# Version_1.net
KiCad netlist of a schematic drawn in EAGLE
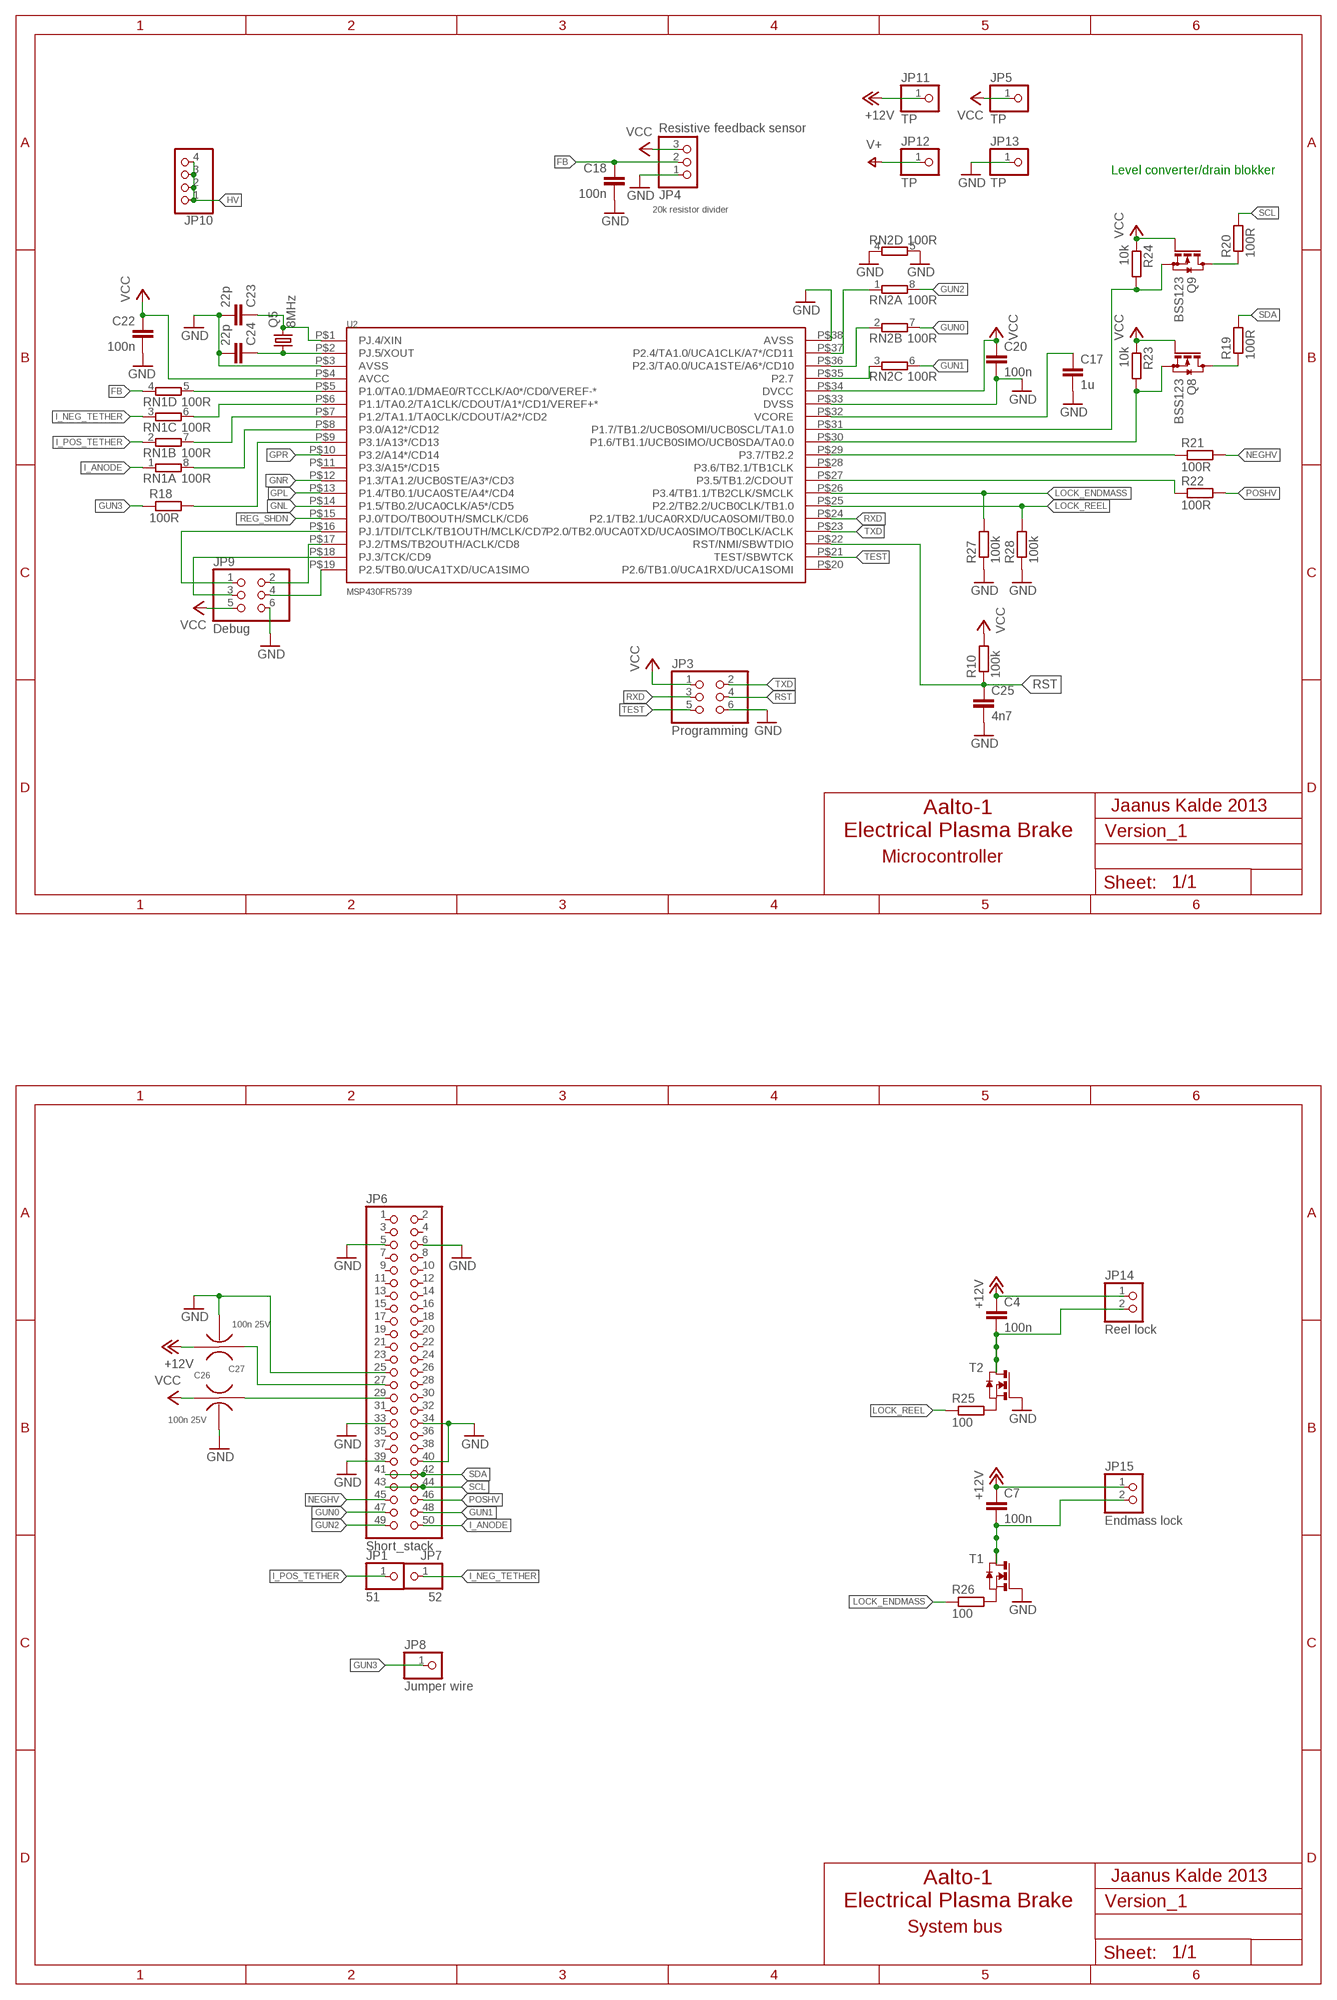
[diagram p0: schematic, sheet 1, part 1 of 2]
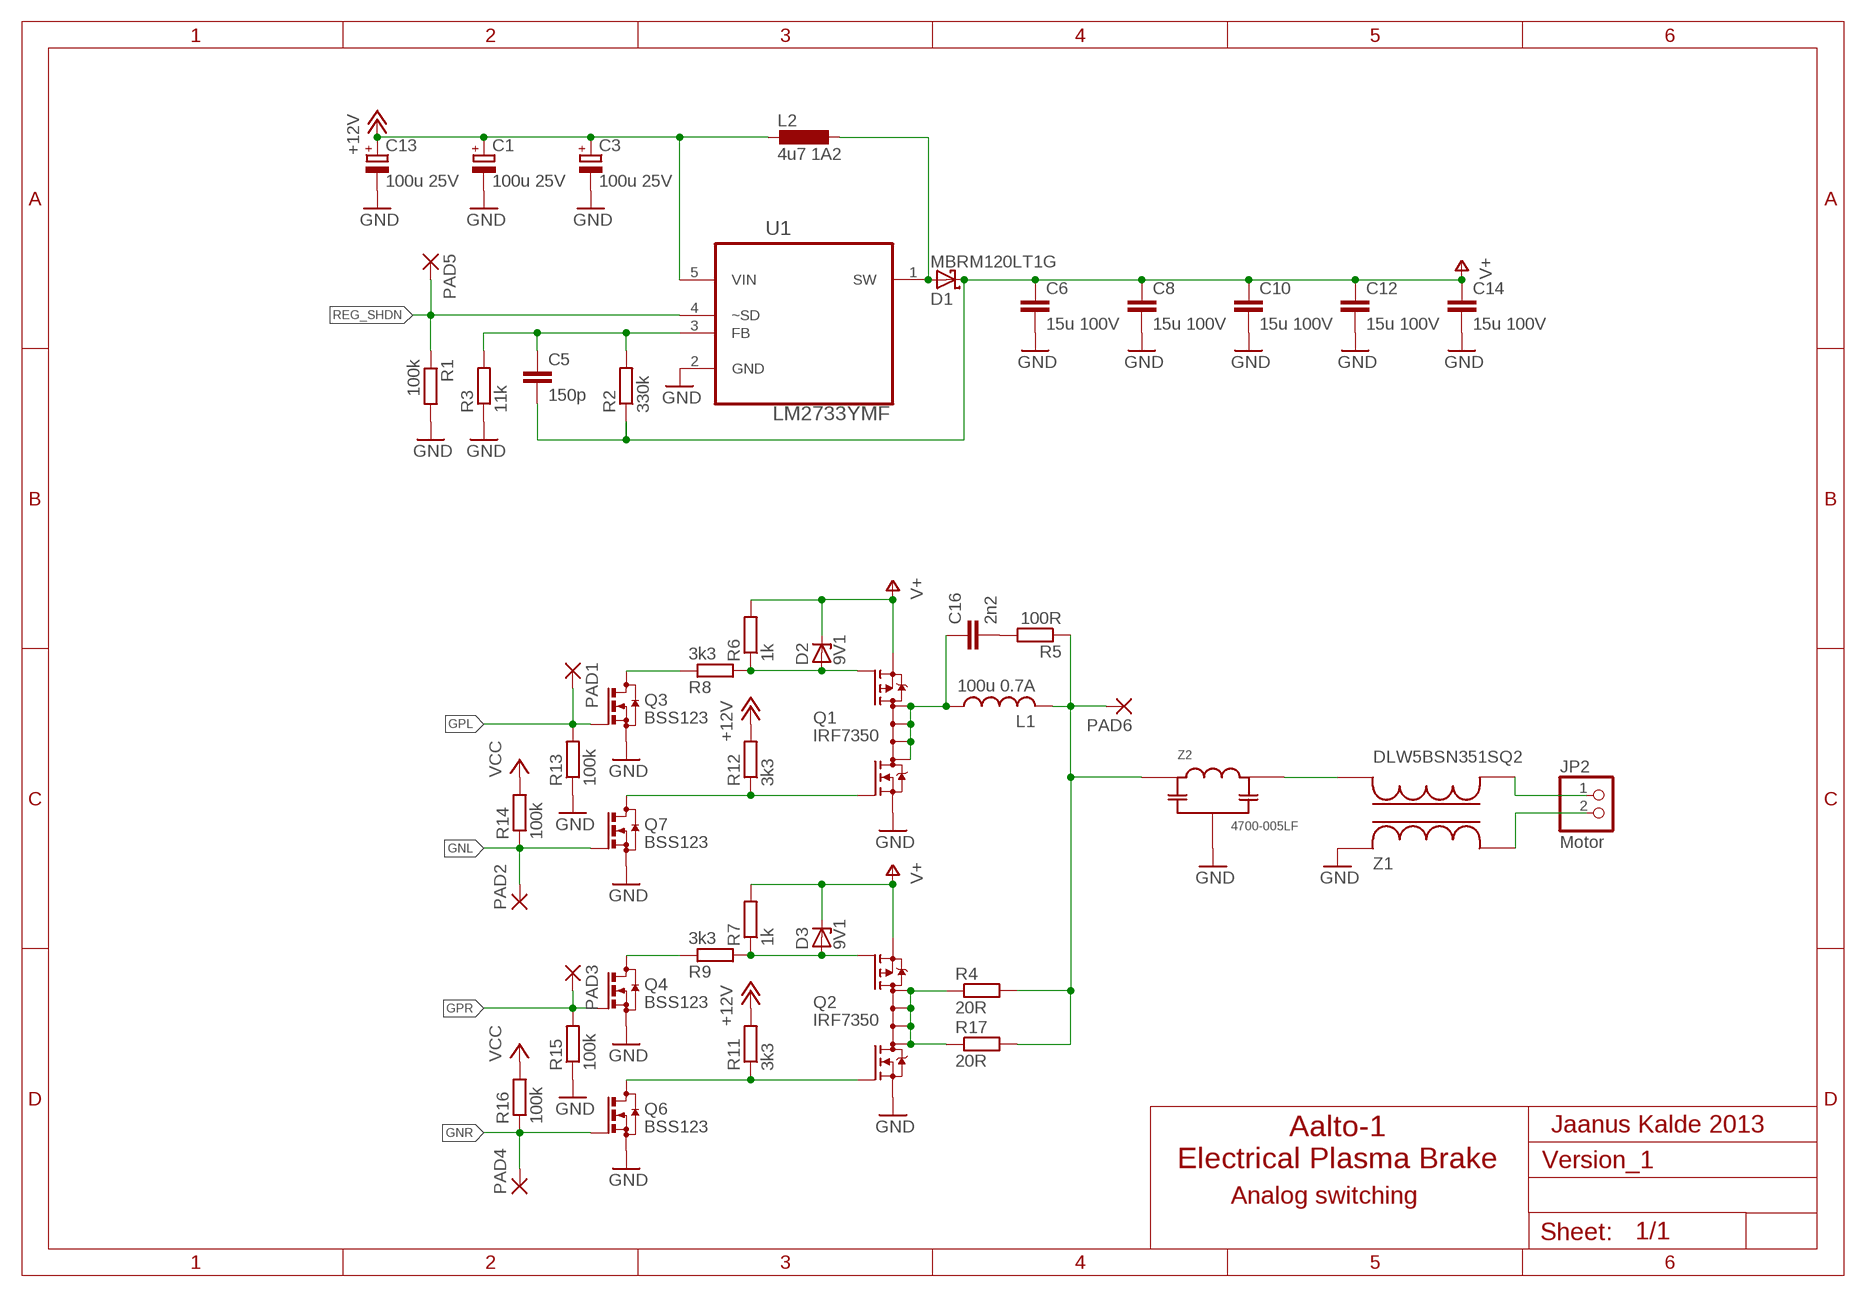
[diagram p1: schematic, sheet 1, part 2 of 2]

(export (version "E")
  (design (tool "Eeschema 10.0.6"))
  (components
    (comp (ref "C1")
      (value "100u 25V")
      (footprint "eagle-import:SMC_E")
      (libsource (lib "eagle-import") (part "CPOL-EUSMCE"))
    )
    (comp (ref "C3")
      (value "100u 25V")
      (footprint "eagle-import:SMC_E")
      (libsource (lib "eagle-import") (part "CPOL-EUSMCE"))
    )
    (comp (ref "C4")
      (value "100n")
      (footprint "eagle-import:C0603")
      (libsource (lib "eagle-import") (part "C-EUC0603"))
    )
    (comp (ref "C5")
      (value "150p")
      (footprint "eagle-import:C0603K")
      (libsource (lib "eagle-import") (part "C-EUC0603K"))
    )
    (comp (ref "C6")
      (value "15u 100V")
      (footprint "eagle-import:C2220K")
      (libsource (lib "eagle-import") (part "C-EUC2220K"))
    )
    (comp (ref "C7")
      (value "100n")
      (footprint "eagle-import:C0603")
      (libsource (lib "eagle-import") (part "C-EUC0603"))
    )
    (comp (ref "C8")
      (value "15u 100V")
      (footprint "eagle-import:C2220K")
      (libsource (lib "eagle-import") (part "C-EUC2220K"))
    )
    (comp (ref "C10")
      (value "15u 100V")
      (footprint "eagle-import:C2220K")
      (libsource (lib "eagle-import") (part "C-EUC2220K"))
    )
    (comp (ref "C12")
      (value "15u 100V")
      (footprint "eagle-import:C2220K")
      (libsource (lib "eagle-import") (part "C-EUC2220K"))
    )
    (comp (ref "C13")
      (value "100u 25V")
      (footprint "eagle-import:SMC_E")
      (libsource (lib "eagle-import") (part "CPOL-EUSMCE"))
    )
    (comp (ref "C14")
      (value "15u 100V")
      (footprint "eagle-import:C2220K")
      (libsource (lib "eagle-import") (part "C-EUC2220K"))
    )
    (comp (ref "C16")
      (value "2n2")
      (footprint "eagle-import:C0805")
      (libsource (lib "eagle-import") (part "C-EUC0805"))
    )
    (comp (ref "C17")
      (value "1u")
      (footprint "eagle-import:C0603K")
      (libsource (lib "eagle-import") (part "C-EUC0603K"))
    )
    (comp (ref "C18")
      (value "100n")
      (footprint "eagle-import:C0603K")
      (libsource (lib "eagle-import") (part "C-EUC0603K"))
    )
    (comp (ref "C20")
      (value "100n")
      (footprint "eagle-import:C0603K")
      (libsource (lib "eagle-import") (part "C-EUC0603K"))
    )
    (comp (ref "C22")
      (value "100n")
      (footprint "eagle-import:C0603")
      (libsource (lib "eagle-import") (part "C-EUC0603"))
    )
    (comp (ref "C23")
      (value "22p")
      (footprint "eagle-import:C0603")
      (libsource (lib "eagle-import") (part "C-EUC0603"))
    )
    (comp (ref "C24")
      (value "22p")
      (footprint "eagle-import:C0603")
      (libsource (lib "eagle-import") (part "C-EUC0603"))
    )
    (comp (ref "C25")
      (value "4n7")
      (footprint "eagle-import:C0603")
      (libsource (lib "eagle-import") (part "C-EUC0603"))
    )
    (comp (ref "C26")
      (value "100n 25V")
      (footprint "eagle-import:0805-3TERM")
      (libsource (lib "eagle-import") (part "CAP-3TERM"))
    )
    (comp (ref "C27")
      (value "100n 25V")
      (footprint "eagle-import:0805-3TERM")
      (libsource (lib "eagle-import") (part "CAP-3TERM"))
    )
    (comp (ref "D1")
      (value "MBRM120LT1G")
      (footprint "eagle-import:POWERMITE")
      (libsource (lib "eagle-import") (part "MBRM120LT1G"))
    )
    (comp (ref "D2")
      (value "9V1")
      (footprint "eagle-import:SOD80C")
      (libsource (lib "eagle-import") (part "ZENER-DIODESOD80C"))
    )
    (comp (ref "D3")
      (value "9V1")
      (footprint "eagle-import:SOD80C")
      (libsource (lib "eagle-import") (part "ZENER-DIODESOD80C"))
    )
    (comp (ref "JP1")
      (value "51")
      (footprint "eagle-import:1X01")
      (libsource (lib "eagle-import") (part "PINHD-1X1"))
    )
    (comp (ref "JP2")
      (value "Motor")
      (footprint "eagle-import:1X02M")
      (libsource (lib "eagle-import") (part "PINHD-1X02_2.00"))
    )
    (comp (ref "JP3")
      (value "Programming")
      (footprint "eagle-import:MICROMATCH-6")
      (libsource (lib "eagle-import") (part "PINHD-2X03_MICROMATCH"))
    )
    (comp (ref "JP4")
      (value "Resistive feedback sensor")
      (footprint "eagle-import:1X03M")
      (libsource (lib "eagle-import") (part "PINHD-1X03_2.00"))
    )
    (comp (ref "JP5")
      (value "TP")
      (footprint "eagle-import:1X01")
      (libsource (lib "eagle-import") (part "PINHD-1X1"))
    )
    (comp (ref "JP6")
      (value "Short_stack")
      (footprint "eagle-import:2X25")
      (libsource (lib "eagle-import") (part "PINHD-2X25"))
    )
    (comp (ref "JP7")
      (value "52")
      (footprint "eagle-import:1X01")
      (libsource (lib "eagle-import") (part "PINHD-1X1"))
    )
    (comp (ref "JP8")
      (value "Jumper wire")
      (footprint "eagle-import:1X01")
      (libsource (lib "eagle-import") (part "PINHD-1X1"))
    )
    (comp (ref "JP9")
      (value "Debug")
      (footprint "eagle-import:MICROMATCH-6")
      (libsource (lib "eagle-import") (part "PINHD-2X03_MICROMATCH"))
    )
    (comp (ref "JP10")
      (value "PINHD-1X4")
      (footprint "eagle-import:1X04")
      (libsource (lib "eagle-import") (part "PINHD-1X4"))
    )
    (comp (ref "JP11")
      (value "TP")
      (footprint "eagle-import:1X01")
      (libsource (lib "eagle-import") (part "PINHD-1X1"))
    )
    (comp (ref "JP12")
      (value "TP")
      (footprint "eagle-import:1X01")
      (libsource (lib "eagle-import") (part "PINHD-1X1"))
    )
    (comp (ref "JP13")
      (value "TP")
      (footprint "eagle-import:1X01")
      (libsource (lib "eagle-import") (part "PINHD-1X1"))
    )
    (comp (ref "JP14")
      (value "Reel lock")
      (footprint "eagle-import:1X02M")
      (libsource (lib "eagle-import") (part "PINHD-1X02_2.00"))
    )
    (comp (ref "JP15")
      (value "Endmass lock")
      (footprint "eagle-import:1X02M")
      (libsource (lib "eagle-import") (part "PINHD-1X02_2.00"))
    )
    (comp (ref "L1")
      (value "100u 0.7A")
      (footprint "eagle-import:L-SMD-7.3")
      (libsource (lib "eagle-import") (part "L-SMD-7.3"))
    )
    (comp (ref "L2")
      (value "4u7 1A2")
      (footprint "eagle-import:SRR4011")
      (libsource (lib "eagle-import") (part "SRR4011"))
    )
    (comp (ref "PAD1")
      (value "WIREPAD1,6/0,8")
      (footprint "eagle-import:1,6_0,8")
      (libsource (lib "eagle-import") (part "WIREPAD1,6/0,8"))
    )
    (comp (ref "PAD2")
      (value "WIREPAD1,6/0,8")
      (footprint "eagle-import:1,6_0,8")
      (libsource (lib "eagle-import") (part "WIREPAD1,6/0,8"))
    )
    (comp (ref "PAD3")
      (value "WIREPAD1,6/0,8")
      (footprint "eagle-import:1,6_0,8")
      (libsource (lib "eagle-import") (part "WIREPAD1,6/0,8"))
    )
    (comp (ref "PAD4")
      (value "WIREPAD1,6/0,8")
      (footprint "eagle-import:1,6_0,8")
      (libsource (lib "eagle-import") (part "WIREPAD1,6/0,8"))
    )
    (comp (ref "PAD5")
      (value "WIREPAD1,6/0,8")
      (footprint "eagle-import:1,6_0,8")
      (libsource (lib "eagle-import") (part "WIREPAD1,6/0,8"))
    )
    (comp (ref "PAD6")
      (value "WIREPAD1,6/0,8")
      (footprint "eagle-import:1,6_0,8")
      (libsource (lib "eagle-import") (part "WIREPAD1,6/0,8"))
    )
    (comp (ref "Q1")
      (value "IRF7350")
      (footprint "eagle-import:SO08-IRF")
      (libsource (lib "eagle-import") (part "IRF7389"))
    )
    (comp (ref "Q2")
      (value "IRF7350")
      (footprint "eagle-import:SO08-IRF")
      (libsource (lib "eagle-import") (part "IRF7389"))
    )
    (comp (ref "Q3")
      (value "BSS123")
      (footprint "eagle-import:SOT23")
      (libsource (lib "eagle-import") (part "BSS123"))
    )
    (comp (ref "Q4")
      (value "BSS123")
      (footprint "eagle-import:SOT23")
      (libsource (lib "eagle-import") (part "BSS123"))
    )
    (comp (ref "Q5")
      (value "8MHz")
      (footprint "eagle-import:HC49U-V")
      (libsource (lib "eagle-import") (part "CRYSTALHC49UV"))
    )
    (comp (ref "Q6")
      (value "BSS123")
      (footprint "eagle-import:SOT23")
      (libsource (lib "eagle-import") (part "BSS123"))
    )
    (comp (ref "Q7")
      (value "BSS123")
      (footprint "eagle-import:SOT23")
      (libsource (lib "eagle-import") (part "BSS123"))
    )
    (comp (ref "Q8")
      (value "BSS123")
      (footprint "eagle-import:SOT23")
      (libsource (lib "eagle-import") (part "BSS123"))
    )
    (comp (ref "Q9")
      (value "BSS123")
      (footprint "eagle-import:SOT23")
      (libsource (lib "eagle-import") (part "BSS123"))
    )
    (comp (ref "R1")
      (value "100k")
      (footprint "eagle-import:R0603")
      (libsource (lib "eagle-import") (part "R-EU_R0603"))
    )
    (comp (ref "R2")
      (value "330k")
      (footprint "eagle-import:R0603")
      (libsource (lib "eagle-import") (part "R-EU_R0603"))
    )
    (comp (ref "R3")
      (value "11k")
      (footprint "eagle-import:R0603")
      (libsource (lib "eagle-import") (part "R-EU_R0603"))
    )
    (comp (ref "R4")
      (value "20R")
      (footprint "eagle-import:R2512")
      (libsource (lib "eagle-import") (part "R-EU_R2512"))
    )
    (comp (ref "R5")
      (value "100R")
      (footprint "eagle-import:R0805")
      (libsource (lib "eagle-import") (part "R-EU_R0805"))
    )
    (comp (ref "R6")
      (value "1k")
      (footprint "eagle-import:R0805")
      (libsource (lib "eagle-import") (part "R-EU_R0805"))
    )
    (comp (ref "R7")
      (value "1k")
      (footprint "eagle-import:R0805")
      (libsource (lib "eagle-import") (part "R-EU_R0805"))
    )
    (comp (ref "R8")
      (value "3k3")
      (footprint "eagle-import:R0805")
      (libsource (lib "eagle-import") (part "R-EU_R0805"))
    )
    (comp (ref "R9")
      (value "3k3")
      (footprint "eagle-import:R0805")
      (libsource (lib "eagle-import") (part "R-EU_R0805"))
    )
    (comp (ref "R10")
      (value "100k")
      (footprint "eagle-import:R0603")
      (libsource (lib "eagle-import") (part "R-EU_R0603"))
    )
    (comp (ref "R11")
      (value "3k3")
      (footprint "eagle-import:R0805")
      (libsource (lib "eagle-import") (part "R-EU_R0805"))
    )
    (comp (ref "R12")
      (value "3k3")
      (footprint "eagle-import:R0805")
      (libsource (lib "eagle-import") (part "R-EU_R0805"))
    )
    (comp (ref "R13")
      (value "100k")
      (footprint "eagle-import:R0603")
      (libsource (lib "eagle-import") (part "R-EU_R0603"))
    )
    (comp (ref "R14")
      (value "100k")
      (footprint "eagle-import:R0603")
      (libsource (lib "eagle-import") (part "R-EU_R0603"))
    )
    (comp (ref "R15")
      (value "100k")
      (footprint "eagle-import:R0603")
      (libsource (lib "eagle-import") (part "R-EU_R0603"))
    )
    (comp (ref "R16")
      (value "100k")
      (footprint "eagle-import:R0603")
      (libsource (lib "eagle-import") (part "R-EU_R0603"))
    )
    (comp (ref "R17")
      (value "20R")
      (footprint "eagle-import:R2512")
      (libsource (lib "eagle-import") (part "R-EU_R2512"))
    )
    (comp (ref "R18")
      (value "100R")
      (footprint "eagle-import:R0603")
      (libsource (lib "eagle-import") (part "R-EU_R0603"))
    )
    (comp (ref "R19")
      (value "100R")
      (footprint "eagle-import:R0603")
      (libsource (lib "eagle-import") (part "R-EU_R0603"))
    )
    (comp (ref "R20")
      (value "100R")
      (footprint "eagle-import:R0603")
      (libsource (lib "eagle-import") (part "R-EU_R0603"))
    )
    (comp (ref "R21")
      (value "100R")
      (footprint "eagle-import:R0603")
      (libsource (lib "eagle-import") (part "R-EU_R0603"))
    )
    (comp (ref "R22")
      (value "100R")
      (footprint "eagle-import:R0603")
      (libsource (lib "eagle-import") (part "R-EU_R0603"))
    )
    (comp (ref "R23")
      (value "10k")
      (footprint "eagle-import:R0603")
      (libsource (lib "eagle-import") (part "R-EU_R0603"))
    )
    (comp (ref "R24")
      (value "10k")
      (footprint "eagle-import:R0603")
      (libsource (lib "eagle-import") (part "R-EU_R0603"))
    )
    (comp (ref "R25")
      (value "100")
      (footprint "eagle-import:R0603")
      (libsource (lib "eagle-import") (part "R-EU_R0603"))
    )
    (comp (ref "R26")
      (value "100")
      (footprint "eagle-import:R0603")
      (libsource (lib "eagle-import") (part "R-EU_R0603"))
    )
    (comp (ref "R27")
      (value "100k")
      (footprint "eagle-import:R0603")
      (libsource (lib "eagle-import") (part "R-EU_R0603"))
    )
    (comp (ref "R28")
      (value "100k")
      (footprint "eagle-import:R0603")
      (libsource (lib "eagle-import") (part "R-EU_R0603"))
    )
    (comp (ref "RN1")
      (value "100R")
      (footprint "eagle-import:EXBN8V")
      (fields (field (name "OC_FARNELL") "unknown") (field (name "OC_NEWARK") "unknown"))
      (libsource (lib "eagle-import") (part "4R-NEXBN8V"))
    )
    (comp (ref "RN2")
      (value "100R")
      (footprint "eagle-import:EXBN8V")
      (libsource (lib "eagle-import") (part "4R-NEXBN8V"))
    )
    (comp (ref "T1")
      (value "NMOSSOT23-6")
      (footprint "eagle-import:SOT23-6")
      (libsource (lib "eagle-import") (part "NMOSSOT23-6"))
    )
    (comp (ref "T2")
      (value "NMOSSOT23-6")
      (footprint "eagle-import:SOT23-6")
      (fields (field (name "OC_FARNELL") "unknown") (field (name "OC_NEWARK") "unknown"))
      (libsource (lib "eagle-import") (part "NMOSSOT23-6"))
    )
    (comp (ref "U1")
      (value "LM2733YMF")
      (footprint "eagle-import:SOT95P284X119-5N")
      (libsource (lib "eagle-import") (part "LM2733YMF"))
    )
    (comp (ref "U2")
      (value "MSP430FR5739")
      (footprint "eagle-import:TSSOP38")
      (libsource (lib "eagle-import") (part "MSP430FR5739"))
    )
    (comp (ref "Z1")
      (value "DLW5BSN351SQ2")
      (footprint "eagle-import:DLW5BS")
      (libsource (lib "eagle-import") (part "DLW5BS"))
    )
    (comp (ref "Z2")
      (value "4700-005LF")
      (footprint "eagle-import:FILTER-PI")
      (libsource (lib "eagle-import") (part "FILTER-PI"))
    )
  )
  (nets
    (net (code "1") (name "+12V") (class "Default")
      (node (ref "C1") (pin "+") (pinfunction "+_+") (pintype "passive"))
      (node (ref "C13") (pin "+") (pinfunction "+_+") (pintype "passive"))
      (node (ref "C26") (pin "P$1") (pinfunction "P$1_P$1") (pintype "bidirectional"))
      (node (ref "C3") (pin "+") (pinfunction "+_+") (pintype "passive"))
      (node (ref "C4") (pin "1") (pinfunction "1_1") (pintype "passive"))
      (node (ref "C7") (pin "1") (pinfunction "1_1") (pintype "passive"))
      (node (ref "JP11") (pin "1") (pinfunction "1_1") (pintype "passive"))
      (node (ref "JP14") (pin "1") (pinfunction "1_1") (pintype "passive"))
      (node (ref "JP15") (pin "1") (pinfunction "1_1") (pintype "passive"))
      (node (ref "L2") (pin "P$1") (pinfunction "1_P$1") (pintype "passive"))
      (node (ref "R11") (pin "2") (pinfunction "2_2") (pintype "passive"))
      (node (ref "R12") (pin "2") (pinfunction "2_2") (pintype "passive"))
      (node (ref "U1") (pin "5") (pinfunction "VIN_5") (pintype "power_in"))
    )
    (net (code "2") (name "FB") (class "Default")
      (node (ref "C18") (pin "1") (pinfunction "1_1") (pintype "passive"))
      (node (ref "JP4") (pin "2") (pinfunction "2_2") (pintype "passive"))
      (node (ref "RN1") (pin "4") (pinfunction "1_4") (pintype "passive"))
    )
    (net (code "3") (name "GND") (class "Default")
      (node (ref "C1") (pin "-") (pinfunction "-_-") (pintype "passive"))
      (node (ref "C10") (pin "2") (pinfunction "2_2") (pintype "passive"))
      (node (ref "C12") (pin "2") (pinfunction "2_2") (pintype "passive"))
      (node (ref "C13") (pin "-") (pinfunction "-_-") (pintype "passive"))
      (node (ref "C14") (pin "2") (pinfunction "2_2") (pintype "passive"))
      (node (ref "C17") (pin "2") (pinfunction "2_2") (pintype "passive"))
      (node (ref "C18") (pin "2") (pinfunction "2_2") (pintype "passive"))
      (node (ref "C20") (pin "2") (pinfunction "2_2") (pintype "passive"))
      (node (ref "C22") (pin "2") (pinfunction "2_2") (pintype "passive"))
      (node (ref "C23") (pin "2") (pinfunction "2_2") (pintype "passive"))
      (node (ref "C24") (pin "2") (pinfunction "2_2") (pintype "passive"))
      (node (ref "C25") (pin "2") (pinfunction "2_2") (pintype "passive"))
      (node (ref "C26") (pin "P$2") (pinfunction "P$2_P$2") (pintype "bidirectional"))
      (node (ref "C27") (pin "P$2") (pinfunction "P$2_P$2") (pintype "bidirectional"))
      (node (ref "C3") (pin "-") (pinfunction "-_-") (pintype "passive"))
      (node (ref "C6") (pin "2") (pinfunction "2_2") (pintype "passive"))
      (node (ref "C8") (pin "2") (pinfunction "2_2") (pintype "passive"))
      (node (ref "JP13") (pin "1") (pinfunction "1_1") (pintype "passive"))
      (node (ref "JP3") (pin "6") (pinfunction "6_6") (pintype "passive"))
      (node (ref "JP4") (pin "1") (pinfunction "1_1") (pintype "passive"))
      (node (ref "JP6") (pin "25") (pinfunction "25_25") (pintype "passive"))
      (node (ref "JP6") (pin "33") (pinfunction "33_33") (pintype "passive"))
      (node (ref "JP6") (pin "34") (pinfunction "34_34") (pintype "passive"))
      (node (ref "JP6") (pin "39") (pinfunction "39_39") (pintype "passive"))
      (node (ref "JP6") (pin "40") (pinfunction "40_40") (pintype "passive"))
      (node (ref "JP6") (pin "5") (pinfunction "5_5") (pintype "passive"))
      (node (ref "JP6") (pin "6") (pinfunction "6_6") (pintype "passive"))
      (node (ref "JP9") (pin "6") (pinfunction "6_6") (pintype "passive"))
      (node (ref "Q1") (pin "1") (pinfunction "N-S_1") (pintype "passive"))
      (node (ref "Q2") (pin "1") (pinfunction "N-S_1") (pintype "passive"))
      (node (ref "Q3") (pin "2") (pinfunction "S_2") (pintype "passive"))
      (node (ref "Q4") (pin "2") (pinfunction "S_2") (pintype "passive"))
      (node (ref "Q6") (pin "2") (pinfunction "S_2") (pintype "passive"))
      (node (ref "Q7") (pin "2") (pinfunction "S_2") (pintype "passive"))
      (node (ref "R1") (pin "2") (pinfunction "2_2") (pintype "passive"))
      (node (ref "R13") (pin "1") (pinfunction "1_1") (pintype "passive"))
      (node (ref "R15") (pin "1") (pinfunction "1_1") (pintype "passive"))
      (node (ref "R27") (pin "1") (pinfunction "1_1") (pintype "passive"))
      (node (ref "R28") (pin "1") (pinfunction "1_1") (pintype "passive"))
      (node (ref "R3") (pin "1") (pinfunction "1_1") (pintype "passive"))
      (node (ref "RN2") (pin "4") (pinfunction "1_4") (pintype "passive"))
      (node (ref "RN2") (pin "5") (pinfunction "2_5") (pintype "passive"))
      (node (ref "T1") (pin "4") (pinfunction "G_4") (pintype "passive"))
      (node (ref "T2") (pin "4") (pinfunction "G_4") (pintype "passive"))
      (node (ref "U1") (pin "2") (pinfunction "GND_2") (pintype "passive"))
      (node (ref "U2") (pin "P$3") (pinfunction "AVSS_P$3") (pintype "bidirectional"))
      (node (ref "U2") (pin "P$33") (pinfunction "DVSS_P$33") (pintype "bidirectional"))
      (node (ref "U2") (pin "P$38") (pinfunction "AVSS_P$38") (pintype "bidirectional"))
      (node (ref "Z1") (pin "P$2") (pinfunction "P$1_P$2") (pintype "bidirectional"))
      (node (ref "Z2") (pin "P$2") (pinfunction "P$3_P$2") (pintype "bidirectional"))
    )
    (net (code "4") (name "GNL") (class "Default")
      (node (ref "PAD2") (pin "1") (pinfunction "P_1") (pintype "passive"))
      (node (ref "Q7") (pin "1") (pinfunction "G_1") (pintype "passive"))
      (node (ref "R14") (pin "1") (pinfunction "1_1") (pintype "passive"))
      (node (ref "U2") (pin "P$14") (pinfunction "P1.5/TB0.2/UCA0CLK/A5*/CD5_P$14") (pintype "bidirectional"))
    )
    (net (code "5") (name "GNR") (class "Default")
      (node (ref "PAD4") (pin "1") (pinfunction "P_1") (pintype "passive"))
      (node (ref "Q6") (pin "1") (pinfunction "G_1") (pintype "passive"))
      (node (ref "R16") (pin "1") (pinfunction "1_1") (pintype "passive"))
      (node (ref "U2") (pin "P$12") (pinfunction "P1.3/TA1.2/UCB0STE/A3*/CD3_P$12") (pintype "bidirectional"))
    )
    (net (code "6") (name "GPL") (class "Default")
      (node (ref "PAD1") (pin "1") (pinfunction "P_1") (pintype "passive"))
      (node (ref "Q3") (pin "1") (pinfunction "G_1") (pintype "passive"))
      (node (ref "R13") (pin "2") (pinfunction "2_2") (pintype "passive"))
      (node (ref "U2") (pin "P$13") (pinfunction "P1.4/TB0.1/UCA0STE/A4*/CD4_P$13") (pintype "bidirectional"))
    )
    (net (code "7") (name "GPR") (class "Default")
      (node (ref "PAD3") (pin "1") (pinfunction "P_1") (pintype "passive"))
      (node (ref "Q4") (pin "1") (pinfunction "G_1") (pintype "passive"))
      (node (ref "R15") (pin "2") (pinfunction "2_2") (pintype "passive"))
      (node (ref "U2") (pin "P$10") (pinfunction "P3.2/A14*/CD14_P$10") (pintype "bidirectional"))
    )
    (net (code "8") (name "GUN0") (class "Default")
      (node (ref "JP6") (pin "47") (pinfunction "47_47") (pintype "passive"))
      (node (ref "RN2") (pin "7") (pinfunction "2_7") (pintype "passive"))
    )
    (net (code "9") (name "GUN1") (class "Default")
      (node (ref "JP6") (pin "48") (pinfunction "48_48") (pintype "passive"))
      (node (ref "RN2") (pin "6") (pinfunction "2_6") (pintype "passive"))
    )
    (net (code "10") (name "GUN2") (class "Default")
      (node (ref "JP6") (pin "49") (pinfunction "49_49") (pintype "passive"))
      (node (ref "RN2") (pin "8") (pinfunction "2_8") (pintype "passive"))
    )
    (net (code "11") (name "GUN3") (class "Default")
      (node (ref "JP8") (pin "1") (pinfunction "1_1") (pintype "passive"))
      (node (ref "R18") (pin "1") (pinfunction "1_1") (pintype "passive"))
    )
    (net (code "12") (name "HV") (class "Default")
      (node (ref "JP10") (pin "1") (pinfunction "1_1") (pintype "passive"))
      (node (ref "JP10") (pin "2") (pinfunction "2_2") (pintype "passive"))
      (node (ref "JP10") (pin "3") (pinfunction "3_3") (pintype "passive"))
      (node (ref "JP10") (pin "4") (pinfunction "4_4") (pintype "passive"))
    )
    (net (code "13") (name "I_ANODE") (class "Default")
      (node (ref "JP6") (pin "50") (pinfunction "50_50") (pintype "passive"))
      (node (ref "RN1") (pin "1") (pinfunction "1_1") (pintype "passive"))
    )
    (net (code "14") (name "I_NEG_TETHER") (class "Default")
      (node (ref "JP7") (pin "1") (pinfunction "1_1") (pintype "passive"))
      (node (ref "RN1") (pin "3") (pinfunction "1_3") (pintype "passive"))
    )
    (net (code "15") (name "I_POS_TETHER") (class "Default")
      (node (ref "JP1") (pin "1") (pinfunction "1_1") (pintype "passive"))
      (node (ref "RN1") (pin "2") (pinfunction "1_2") (pintype "passive"))
    )
    (net (code "16") (name "LOCK_ENDMASS") (class "Default")
      (node (ref "R26") (pin "1") (pinfunction "1_1") (pintype "passive"))
      (node (ref "R27") (pin "2") (pinfunction "2_2") (pintype "passive"))
      (node (ref "U2") (pin "P$26") (pinfunction "P3.4/TB1.1/TB2CLK/SMCLK_P$26") (pintype "bidirectional"))
    )
    (net (code "17") (name "LOCK_REEL") (class "Default")
      (node (ref "R25") (pin "1") (pinfunction "1_1") (pintype "passive"))
      (node (ref "R28") (pin "2") (pinfunction "2_2") (pintype "passive"))
      (node (ref "U2") (pin "P$25") (pinfunction "P2.2/TB2.2/UCB0CLK/TB1.0_P$25") (pintype "bidirectional"))
    )
    (net (code "18") (name "NEGHV") (class "Default")
      (node (ref "JP6") (pin "45") (pinfunction "45_45") (pintype "passive"))
      (node (ref "R21") (pin "2") (pinfunction "2_2") (pintype "passive"))
    )
    (net (code "19") (name "Net-(C16-Pad2)") (class "Default")
      (node (ref "C16") (pin "2") (pinfunction "2_2") (pintype "passive"))
      (node (ref "R5") (pin "2") (pinfunction "2_2") (pintype "passive"))
    )
    (net (code "20") (name "Net-(C26-PadP$3)") (class "Default")
      (node (ref "C26") (pin "P$3") (pinfunction "P$3_P$3") (pintype "bidirectional"))
      (node (ref "JP6") (pin "27") (pinfunction "27_27") (pintype "passive"))
    )
    (net (code "21") (name "Net-(C27-PadP$1)") (class "Default")
      (node (ref "C27") (pin "P$1") (pinfunction "P$1_P$1") (pintype "bidirectional"))
      (node (ref "JP6") (pin "29") (pinfunction "29_29") (pintype "passive"))
    )
    (net (code "22") (name "Net-(D1-A)") (class "Default")
      (node (ref "D1") (pin "2") (pinfunction "A_2") (pintype "passive"))
      (node (ref "L2") (pin "P$2") (pinfunction "2_P$2") (pintype "passive"))
      (node (ref "U1") (pin "1") (pinfunction "SW_1") (pintype "output"))
    )
    (net (code "23") (name "Net-(JP2-Pad1)") (class "Default")
      (node (ref "JP2") (pin "1") (pinfunction "1_1") (pintype "passive"))
      (node (ref "Z1") (pin "P$4") (pinfunction "P$4_P$4") (pintype "bidirectional"))
    )
    (net (code "24") (name "Net-(L1-1)") (class "Default")
      (node (ref "C16") (pin "1") (pinfunction "1_1") (pintype "passive"))
      (node (ref "L1") (pin "P$1") (pinfunction "1_P$1") (pintype "passive"))
      (node (ref "Q1") (pin "5") (pinfunction "D_5") (pintype "passive"))
      (node (ref "Q1") (pin "6") (pinfunction "D_6") (pintype "passive"))
      (node (ref "Q1") (pin "7") (pinfunction "D_7") (pintype "passive"))
      (node (ref "Q1") (pin "8") (pinfunction "D_8") (pintype "passive"))
    )
    (net (code "25") (name "Net-(L1-2)") (class "Default")
      (node (ref "L1") (pin "P$2") (pinfunction "2_P$2") (pintype "passive"))
      (node (ref "PAD6") (pin "1") (pinfunction "P_1") (pintype "passive"))
      (node (ref "R17") (pin "2") (pinfunction "2_2") (pintype "passive"))
      (node (ref "R4") (pin "2") (pinfunction "2_2") (pintype "passive"))
      (node (ref "R5") (pin "1") (pinfunction "1_1") (pintype "passive"))
      (node (ref "Z2") (pin "P$1") (pinfunction "P$1_P$1") (pintype "bidirectional"))
    )
    (net (code "26") (name "Net-(Q1-N-G)") (class "Default")
      (node (ref "Q1") (pin "2") (pinfunction "N-G_2") (pintype "passive"))
      (node (ref "Q7") (pin "3") (pinfunction "D_3") (pintype "passive"))
      (node (ref "R12") (pin "1") (pinfunction "1_1") (pintype "passive"))
    )
    (net (code "27") (name "Net-(Q1-P-G)") (class "Default")
      (node (ref "D2") (pin "A") (pinfunction "A_A") (pintype "passive"))
      (node (ref "Q1") (pin "4") (pinfunction "P-G_4") (pintype "passive"))
      (node (ref "R6") (pin "1") (pinfunction "1_1") (pintype "passive"))
      (node (ref "R8") (pin "2") (pinfunction "2_2") (pintype "passive"))
    )
    (net (code "28") (name "Net-(Q2-D-Pad5)") (class "Default")
      (node (ref "Q2") (pin "5") (pinfunction "D_5") (pintype "passive"))
      (node (ref "Q2") (pin "6") (pinfunction "D_6") (pintype "passive"))
      (node (ref "Q2") (pin "7") (pinfunction "D_7") (pintype "passive"))
      (node (ref "Q2") (pin "8") (pinfunction "D_8") (pintype "passive"))
      (node (ref "R17") (pin "1") (pinfunction "1_1") (pintype "passive"))
      (node (ref "R4") (pin "1") (pinfunction "1_1") (pintype "passive"))
    )
    (net (code "29") (name "Net-(Q2-N-G)") (class "Default")
      (node (ref "Q2") (pin "2") (pinfunction "N-G_2") (pintype "passive"))
      (node (ref "Q6") (pin "3") (pinfunction "D_3") (pintype "passive"))
      (node (ref "R11") (pin "1") (pinfunction "1_1") (pintype "passive"))
    )
    (net (code "30") (name "Net-(Q2-P-G)") (class "Default")
      (node (ref "D3") (pin "A") (pinfunction "A_A") (pintype "passive"))
      (node (ref "Q2") (pin "4") (pinfunction "P-G_4") (pintype "passive"))
      (node (ref "R7") (pin "1") (pinfunction "1_1") (pintype "passive"))
      (node (ref "R9") (pin "2") (pinfunction "2_2") (pintype "passive"))
    )
    (net (code "31") (name "Net-(Q3-D)") (class "Default")
      (node (ref "Q3") (pin "3") (pinfunction "D_3") (pintype "passive"))
      (node (ref "R8") (pin "1") (pinfunction "1_1") (pintype "passive"))
    )
    (net (code "32") (name "Net-(Q4-D)") (class "Default")
      (node (ref "Q4") (pin "3") (pinfunction "D_3") (pintype "passive"))
      (node (ref "R9") (pin "1") (pinfunction "1_1") (pintype "passive"))
    )
    (net (code "33") (name "Net-(Q8-D)") (class "Default")
      (node (ref "Q8") (pin "3") (pinfunction "D_3") (pintype "passive"))
      (node (ref "R19") (pin "1") (pinfunction "1_1") (pintype "passive"))
    )
    (net (code "34") (name "Net-(Q8-S)") (class "Default")
      (node (ref "Q8") (pin "2") (pinfunction "S_2") (pintype "passive"))
      (node (ref "R23") (pin "2") (pinfunction "2_2") (pintype "passive"))
      (node (ref "U2") (pin "P$30") (pinfunction "P1.6/TB1.1/UCB0SIMO/UCB0SDA/TA0.0_P$30") (pintype "bidirectional"))
    )
    (net (code "35") (name "Net-(Q9-D)") (class "Default")
      (node (ref "Q9") (pin "3") (pinfunction "D_3") (pintype "passive"))
      (node (ref "R20") (pin "1") (pinfunction "1_1") (pintype "passive"))
    )
    (net (code "36") (name "Net-(Q9-S)") (class "Default")
      (node (ref "Q9") (pin "2") (pinfunction "S_2") (pintype "passive"))
      (node (ref "R24") (pin "2") (pinfunction "2_2") (pintype "passive"))
      (node (ref "U2") (pin "P$31") (pinfunction "P1.7/TB1.2/UCB0SOMI/UCB0SCL/TA1.0_P$31") (pintype "bidirectional"))
    )
    (net (code "37") (name "Net-(RN1A-2)") (class "Default")
      (node (ref "RN1") (pin "8") (pinfunction "2_8") (pintype "passive"))
      (node (ref "U2") (pin "P$8") (pinfunction "P3.0/A12*/CD12_P$8") (pintype "bidirectional"))
    )
    (net (code "38") (name "Net-(RN1B-2)") (class "Default")
      (node (ref "RN1") (pin "7") (pinfunction "2_7") (pintype "passive"))
      (node (ref "U2") (pin "P$7") (pinfunction "P1.2/TA1.1/TA0CLK/CDOUT/A2*/CD2_P$7") (pintype "bidirectional"))
    )
    (net (code "39") (name "Net-(RN1C-2)") (class "Default")
      (node (ref "RN1") (pin "6") (pinfunction "2_6") (pintype "passive"))
      (node (ref "U2") (pin "P$6") (pinfunction "P1.1/TA0.2/TA1CLK/CDOUT/A1*/CD1/VEREF+*_P$6") (pintype "bidirectional"))
    )
    (net (code "40") (name "Net-(RN1D-2)") (class "Default")
      (node (ref "RN1") (pin "5") (pinfunction "2_5") (pintype "passive"))
      (node (ref "U2") (pin "P$5") (pinfunction "P1.0/TA0.1/DMAE0/RTCCLK/A0*/CD0/VEREF-*_P$5") (pintype "bidirectional"))
    )
    (net (code "41") (name "Net-(RN2B-1)") (class "Default")
      (node (ref "RN2") (pin "2") (pinfunction "1_2") (pintype "passive"))
      (node (ref "U2") (pin "P$36") (pinfunction "P2.3/TA0.0/UCA1STE/A6*/CD10_P$36") (pintype "bidirectional"))
    )
    (net (code "42") (name "Net-(RN2C-1)") (class "Default")
      (node (ref "RN2") (pin "3") (pinfunction "1_3") (pintype "passive"))
      (node (ref "U2") (pin "P$35") (pinfunction "P2.7_P$35") (pintype "bidirectional"))
    )
    (net (code "43") (name "Net-(T1-D)") (class "Default")
      (node (ref "C7") (pin "2") (pinfunction "2_2") (pintype "passive"))
      (node (ref "JP15") (pin "2") (pinfunction "2_2") (pintype "passive"))
      (node (ref "T1") (pin "1") (pinfunction "D_1") (pintype "passive"))
      (node (ref "T1") (pin "2") (pinfunction "D1_2") (pintype "passive"))
      (node (ref "T1") (pin "5") (pinfunction "D2_5") (pintype "passive"))
      (node (ref "T1") (pin "6") (pinfunction "D3_6") (pintype "passive"))
    )
    (net (code "44") (name "Net-(T1-S)") (class "Default")
      (node (ref "R26") (pin "2") (pinfunction "2_2") (pintype "passive"))
      (node (ref "T1") (pin "3") (pinfunction "S_3") (pintype "passive"))
    )
    (net (code "45") (name "Net-(T2-D)") (class "Default")
      (node (ref "C4") (pin "2") (pinfunction "2_2") (pintype "passive"))
      (node (ref "JP14") (pin "2") (pinfunction "2_2") (pintype "passive"))
      (node (ref "T2") (pin "1") (pinfunction "D_1") (pintype "passive"))
      (node (ref "T2") (pin "2") (pinfunction "D1_2") (pintype "passive"))
      (node (ref "T2") (pin "5") (pinfunction "D2_5") (pintype "passive"))
      (node (ref "T2") (pin "6") (pinfunction "D3_6") (pintype "passive"))
    )
    (net (code "46") (name "Net-(T2-S)") (class "Default")
      (node (ref "R25") (pin "2") (pinfunction "2_2") (pintype "passive"))
      (node (ref "T2") (pin "3") (pinfunction "S_3") (pintype "passive"))
    )
    (net (code "47") (name "Net-(U1-FB)") (class "Default")
      (node (ref "C5") (pin "1") (pinfunction "1_1") (pintype "passive"))
      (node (ref "R2") (pin "2") (pinfunction "2_2") (pintype "passive"))
      (node (ref "R3") (pin "2") (pinfunction "2_2") (pintype "passive"))
      (node (ref "U1") (pin "3") (pinfunction "FB_3") (pintype "input"))
    )
    (net (code "48") (name "Net-(U2-P2.4{slash}TA1.0{slash}UCA1CLK{slash}A7*{slash}CD11)") (class "Default")
      (node (ref "RN2") (pin "1") (pinfunction "1_1") (pintype "passive"))
      (node (ref "U2") (pin "P$37") (pinfunction "P2.4/TA1.0/UCA1CLK/A7*/CD11_P$37") (pintype "bidirectional"))
    )
    (net (code "49") (name "Net-(U2-P2.5{slash}TB0.0{slash}UCA1TXD{slash}UCA1SIMO)") (class "Default")
      (node (ref "JP9") (pin "4") (pinfunction "4_4") (pintype "passive"))
      (node (ref "U2") (pin "P$19") (pinfunction "P2.5/TB0.0/UCA1TXD/UCA1SIMO_P$19") (pintype "bidirectional"))
    )
    (net (code "50") (name "Net-(U2-P3.1{slash}A13*{slash}CD13)") (class "Default")
      (node (ref "R18") (pin "2") (pinfunction "2_2") (pintype "passive"))
      (node (ref "U2") (pin "P$9") (pinfunction "P3.1/A13*/CD13_P$9") (pintype "bidirectional"))
    )
    (net (code "51") (name "Net-(U2-P3.5{slash}TB1.2{slash}CDOUT)") (class "Default")
      (node (ref "R22") (pin "1") (pinfunction "1_1") (pintype "passive"))
      (node (ref "U2") (pin "P$27") (pinfunction "P3.5/TB1.2/CDOUT_P$27") (pintype "bidirectional"))
    )
    (net (code "52") (name "Net-(U2-P3.7{slash}TB2.2)") (class "Default")
      (node (ref "R21") (pin "1") (pinfunction "1_1") (pintype "passive"))
      (node (ref "U2") (pin "P$29") (pinfunction "P3.7/TB2.2_P$29") (pintype "bidirectional"))
    )
    (net (code "53") (name "Net-(U2-PJ.1{slash}TDI{slash}TCLK{slash}TB1OUTH{slash}MCLK{slash}CD7)") (class "Default")
      (node (ref "JP9") (pin "1") (pinfunction "1_1") (pintype "passive"))
      (node (ref "U2") (pin "P$16") (pinfunction "PJ.1/TDI/TCLK/TB1OUTH/MCLK/CD7_P$16") (pintype "bidirectional"))
    )
    (net (code "54") (name "Net-(U2-PJ.2{slash}TMS{slash}TB2OUTH{slash}ACLK{slash}CD8)") (class "Default")
      (node (ref "JP9") (pin "2") (pinfunction "2_2") (pintype "passive"))
      (node (ref "U2") (pin "P$17") (pinfunction "PJ.2/TMS/TB2OUTH/ACLK/CD8_P$17") (pintype "bidirectional"))
    )
    (net (code "55") (name "Net-(U2-PJ.3{slash}TCK{slash}CD9)") (class "Default")
      (node (ref "JP9") (pin "3") (pinfunction "3_3") (pintype "passive"))
      (node (ref "U2") (pin "P$18") (pinfunction "PJ.3/TCK/CD9_P$18") (pintype "bidirectional"))
    )
    (net (code "56") (name "Net-(U2-PJ.4{slash}XIN)") (class "Default")
      (node (ref "C23") (pin "1") (pinfunction "1_1") (pintype "passive"))
      (node (ref "Q5") (pin "2") (pinfunction "2_2") (pintype "passive"))
      (node (ref "U2") (pin "P$1") (pinfunction "PJ.4/XIN_P$1") (pintype "bidirectional"))
    )
    (net (code "57") (name "Net-(U2-PJ.5{slash}XOUT)") (class "Default")
      (node (ref "C24") (pin "1") (pinfunction "1_1") (pintype "passive"))
      (node (ref "Q5") (pin "1") (pinfunction "1_1") (pintype "passive"))
      (node (ref "U2") (pin "P$2") (pinfunction "PJ.5/XOUT_P$2") (pintype "bidirectional"))
    )
    (net (code "58") (name "Net-(U2-VCORE)") (class "Default")
      (node (ref "C17") (pin "1") (pinfunction "1_1") (pintype "passive"))
      (node (ref "U2") (pin "P$32") (pinfunction "VCORE_P$32") (pintype "bidirectional"))
    )
    (net (code "59") (name "Net-(Z1-P$2)") (class "Default")
      (node (ref "JP2") (pin "2") (pinfunction "2_2") (pintype "passive"))
      (node (ref "Z1") (pin "P$1") (pinfunction "P$2_P$1") (pintype "bidirectional"))
    )
    (net (code "60") (name "Net-(Z2-P$2)") (class "Default")
      (node (ref "Z1") (pin "P$3") (pinfunction "P$3_P$3") (pintype "bidirectional"))
      (node (ref "Z2") (pin "P$3") (pinfunction "P$2_P$3") (pintype "bidirectional"))
    )
    (net (code "61") (name "POSHV") (class "Default")
      (node (ref "JP6") (pin "46") (pinfunction "46_46") (pintype "passive"))
      (node (ref "R22") (pin "2") (pinfunction "2_2") (pintype "passive"))
    )
    (net (code "62") (name "REG_SHDN") (class "Default")
      (node (ref "PAD5") (pin "1") (pinfunction "P_1") (pintype "passive"))
      (node (ref "R1") (pin "1") (pinfunction "1_1") (pintype "passive"))
      (node (ref "U1") (pin "4") (pinfunction "~{SD}_4") (pintype "input"))
      (node (ref "U2") (pin "P$15") (pinfunction "PJ.0/TDO/TB0OUTH/SMCLK/CD6_P$15") (pintype "bidirectional"))
    )
    (net (code "63") (name "RST") (class "Default")
      (node (ref "C25") (pin "1") (pinfunction "1_1") (pintype "passive"))
      (node (ref "JP3") (pin "4") (pinfunction "4_4") (pintype "passive"))
      (node (ref "R10") (pin "1") (pinfunction "1_1") (pintype "passive"))
      (node (ref "U2") (pin "P$22") (pinfunction "RST/NMI/SBWTDIO_P$22") (pintype "bidirectional"))
    )
    (net (code "64") (name "RXD") (class "Default")
      (node (ref "JP3") (pin "3") (pinfunction "3_3") (pintype "passive"))
      (node (ref "U2") (pin "P$24") (pinfunction "P2.1/TB2.1/UCA0RXD/UCA0SOMI/TB0.0_P$24") (pintype "bidirectional"))
    )
    (net (code "65") (name "SCL") (class "Default")
      (node (ref "JP6") (pin "43") (pinfunction "43_43") (pintype "passive"))
      (node (ref "JP6") (pin "44") (pinfunction "44_44") (pintype "passive"))
      (node (ref "R20") (pin "2") (pinfunction "2_2") (pintype "passive"))
    )
    (net (code "66") (name "SDA") (class "Default")
      (node (ref "JP6") (pin "41") (pinfunction "41_41") (pintype "passive"))
      (node (ref "JP6") (pin "42") (pinfunction "42_42") (pintype "passive"))
      (node (ref "R19") (pin "2") (pinfunction "2_2") (pintype "passive"))
    )
    (net (code "67") (name "TEST") (class "Default")
      (node (ref "JP3") (pin "5") (pinfunction "5_5") (pintype "passive"))
      (node (ref "U2") (pin "P$21") (pinfunction "TEST/SBWTCK_P$21") (pintype "bidirectional"))
    )
    (net (code "68") (name "TXD") (class "Default")
      (node (ref "JP3") (pin "2") (pinfunction "2_2") (pintype "passive"))
      (node (ref "U2") (pin "P$23") (pinfunction "P2.0/TB2.0/UCA0TXD/UCA0SIMO/TB0CLK/ACLK_P$23") (pintype "bidirectional"))
    )
    (net (code "69") (name "V+") (class "Default")
      (node (ref "C10") (pin "1") (pinfunction "1_1") (pintype "passive"))
      (node (ref "C12") (pin "1") (pinfunction "1_1") (pintype "passive"))
      (node (ref "C14") (pin "1") (pinfunction "1_1") (pintype "passive"))
      (node (ref "C5") (pin "2") (pinfunction "2_2") (pintype "passive"))
      (node (ref "C6") (pin "1") (pinfunction "1_1") (pintype "passive"))
      (node (ref "C8") (pin "1") (pinfunction "1_1") (pintype "passive"))
      (node (ref "D1") (pin "1") (pinfunction "C_1") (pintype "passive"))
      (node (ref "D2") (pin "C") (pinfunction "C_C") (pintype "passive"))
      (node (ref "D3") (pin "C") (pinfunction "C_C") (pintype "passive"))
      (node (ref "JP12") (pin "1") (pinfunction "1_1") (pintype "passive"))
      (node (ref "Q1") (pin "3") (pinfunction "P-S_3") (pintype "passive"))
      (node (ref "Q2") (pin "3") (pinfunction "P-S_3") (pintype "passive"))
      (node (ref "R2") (pin "1") (pinfunction "1_1") (pintype "passive"))
      (node (ref "R6") (pin "2") (pinfunction "2_2") (pintype "passive"))
      (node (ref "R7") (pin "2") (pinfunction "2_2") (pintype "passive"))
    )
    (net (code "70") (name "VCC") (class "Default")
      (node (ref "C20") (pin "1") (pinfunction "1_1") (pintype "passive"))
      (node (ref "C22") (pin "1") (pinfunction "1_1") (pintype "passive"))
      (node (ref "C27") (pin "P$3") (pinfunction "P$3_P$3") (pintype "bidirectional"))
      (node (ref "JP3") (pin "1") (pinfunction "1_1") (pintype "passive"))
      (node (ref "JP4") (pin "3") (pinfunction "3_3") (pintype "passive"))
      (node (ref "JP5") (pin "1") (pinfunction "1_1") (pintype "passive"))
      (node (ref "JP9") (pin "5") (pinfunction "5_5") (pintype "passive"))
      (node (ref "Q8") (pin "1") (pinfunction "G_1") (pintype "passive"))
      (node (ref "Q9") (pin "1") (pinfunction "G_1") (pintype "passive"))
      (node (ref "R10") (pin "2") (pinfunction "2_2") (pintype "passive"))
      (node (ref "R14") (pin "2") (pinfunction "2_2") (pintype "passive"))
      (node (ref "R16") (pin "2") (pinfunction "2_2") (pintype "passive"))
      (node (ref "R23") (pin "1") (pinfunction "1_1") (pintype "passive"))
      (node (ref "R24") (pin "1") (pinfunction "1_1") (pintype "passive"))
      (node (ref "U2") (pin "P$34") (pinfunction "DVCC_P$34") (pintype "bidirectional"))
      (node (ref "U2") (pin "P$4") (pinfunction "AVCC_P$4") (pintype "bidirectional"))
    )
    (net (code "71") (name "unconnected-(JP6-Pad1)") (class "Default")
      (node (ref "JP6") (pin "1") (pinfunction "1_1") (pintype "passive"))
    )
    (net (code "72") (name "unconnected-(JP6-Pad2)") (class "Default")
      (node (ref "JP6") (pin "2") (pinfunction "2_2") (pintype "passive"))
    )
    (net (code "73") (name "unconnected-(JP6-Pad3)") (class "Default")
      (node (ref "JP6") (pin "3") (pinfunction "3_3") (pintype "passive"))
    )
    (net (code "74") (name "unconnected-(JP6-Pad4)") (class "Default")
      (node (ref "JP6") (pin "4") (pinfunction "4_4") (pintype "passive"))
    )
    (net (code "75") (name "unconnected-(JP6-Pad7)") (class "Default")
      (node (ref "JP6") (pin "7") (pinfunction "7_7") (pintype "passive"))
    )
    (net (code "76") (name "unconnected-(JP6-Pad8)") (class "Default")
      (node (ref "JP6") (pin "8") (pinfunction "8_8") (pintype "passive"))
    )
    (net (code "77") (name "unconnected-(JP6-Pad9)") (class "Default")
      (node (ref "JP6") (pin "9") (pinfunction "9_9") (pintype "passive"))
    )
    (net (code "78") (name "unconnected-(JP6-Pad10)") (class "Default")
      (node (ref "JP6") (pin "10") (pinfunction "10_10") (pintype "passive"))
    )
    (net (code "79") (name "unconnected-(JP6-Pad11)") (class "Default")
      (node (ref "JP6") (pin "11") (pinfunction "11_11") (pintype "passive"))
    )
    (net (code "80") (name "unconnected-(JP6-Pad12)") (class "Default")
      (node (ref "JP6") (pin "12") (pinfunction "12_12") (pintype "passive"))
    )
    (net (code "81") (name "unconnected-(JP6-Pad13)") (class "Default")
      (node (ref "JP6") (pin "13") (pinfunction "13_13") (pintype "passive"))
    )
    (net (code "82") (name "unconnected-(JP6-Pad14)") (class "Default")
      (node (ref "JP6") (pin "14") (pinfunction "14_14") (pintype "passive"))
    )
    (net (code "83") (name "unconnected-(JP6-Pad15)") (class "Default")
      (node (ref "JP6") (pin "15") (pinfunction "15_15") (pintype "passive"))
    )
    (net (code "84") (name "unconnected-(JP6-Pad16)") (class "Default")
      (node (ref "JP6") (pin "16") (pinfunction "16_16") (pintype "passive"))
    )
    (net (code "85") (name "unconnected-(JP6-Pad17)") (class "Default")
      (node (ref "JP6") (pin "17") (pinfunction "17_17") (pintype "passive"))
    )
    (net (code "86") (name "unconnected-(JP6-Pad18)") (class "Default")
      (node (ref "JP6") (pin "18") (pinfunction "18_18") (pintype "passive"))
    )
    (net (code "87") (name "unconnected-(JP6-Pad19)") (class "Default")
      (node (ref "JP6") (pin "19") (pinfunction "19_19") (pintype "passive"))
    )
    (net (code "88") (name "unconnected-(JP6-Pad20)") (class "Default")
      (node (ref "JP6") (pin "20") (pinfunction "20_20") (pintype "passive"))
    )
    (net (code "89") (name "unconnected-(JP6-Pad21)") (class "Default")
      (node (ref "JP6") (pin "21") (pinfunction "21_21") (pintype "passive"))
    )
    (net (code "90") (name "unconnected-(JP6-Pad22)") (class "Default")
      (node (ref "JP6") (pin "22") (pinfunction "22_22") (pintype "passive"))
    )
    (net (code "91") (name "unconnected-(JP6-Pad23)") (class "Default")
      (node (ref "JP6") (pin "23") (pinfunction "23_23") (pintype "passive"))
    )
    (net (code "92") (name "unconnected-(JP6-Pad24)") (class "Default")
      (node (ref "JP6") (pin "24") (pinfunction "24_24") (pintype "passive"))
    )
    (net (code "93") (name "unconnected-(JP6-Pad26)") (class "Default")
      (node (ref "JP6") (pin "26") (pinfunction "26_26") (pintype "passive"))
    )
    (net (code "94") (name "unconnected-(JP6-Pad28)") (class "Default")
      (node (ref "JP6") (pin "28") (pinfunction "28_28") (pintype "passive"))
    )
    (net (code "95") (name "unconnected-(JP6-Pad30)") (class "Default")
      (node (ref "JP6") (pin "30") (pinfunction "30_30") (pintype "passive"))
    )
    (net (code "96") (name "unconnected-(JP6-Pad31)") (class "Default")
      (node (ref "JP6") (pin "31") (pinfunction "31_31") (pintype "passive"))
    )
    (net (code "97") (name "unconnected-(JP6-Pad32)") (class "Default")
      (node (ref "JP6") (pin "32") (pinfunction "32_32") (pintype "passive"))
    )
    (net (code "98") (name "unconnected-(JP6-Pad35)") (class "Default")
      (node (ref "JP6") (pin "35") (pinfunction "35_35") (pintype "passive"))
    )
    (net (code "99") (name "unconnected-(JP6-Pad36)") (class "Default")
      (node (ref "JP6") (pin "36") (pinfunction "36_36") (pintype "passive"))
    )
    (net (code "100") (name "unconnected-(JP6-Pad37)") (class "Default")
      (node (ref "JP6") (pin "37") (pinfunction "37_37") (pintype "passive"))
    )
    (net (code "101") (name "unconnected-(JP6-Pad38)") (class "Default")
      (node (ref "JP6") (pin "38") (pinfunction "38_38") (pintype "passive"))
    )
    (net (code "102") (name "unconnected-(U2-P2.6{slash}TB1.0{slash}UCA1RXD{slash}UCA1SOMI-PadP$20)") (class "Default")
      (node (ref "U2") (pin "P$20") (pinfunction "P2.6/TB1.0/UCA1RXD/UCA1SOMI_P$20") (pintype "bidirectional"))
    )
    (net (code "103") (name "unconnected-(U2-P3.3{slash}A15*{slash}CD15-PadP$11)") (class "Default")
      (node (ref "U2") (pin "P$11") (pinfunction "P3.3/A15*/CD15_P$11") (pintype "bidirectional"))
    )
    (net (code "104") (name "unconnected-(U2-P3.6{slash}TB2.1{slash}TB1CLK-PadP$28)") (class "Default")
      (node (ref "U2") (pin "P$28") (pinfunction "P3.6/TB2.1/TB1CLK_P$28") (pintype "bidirectional"))
    )
  )
)
